# vor_add_on.net
KiCad netlist of a schematic drawn in EAGLE
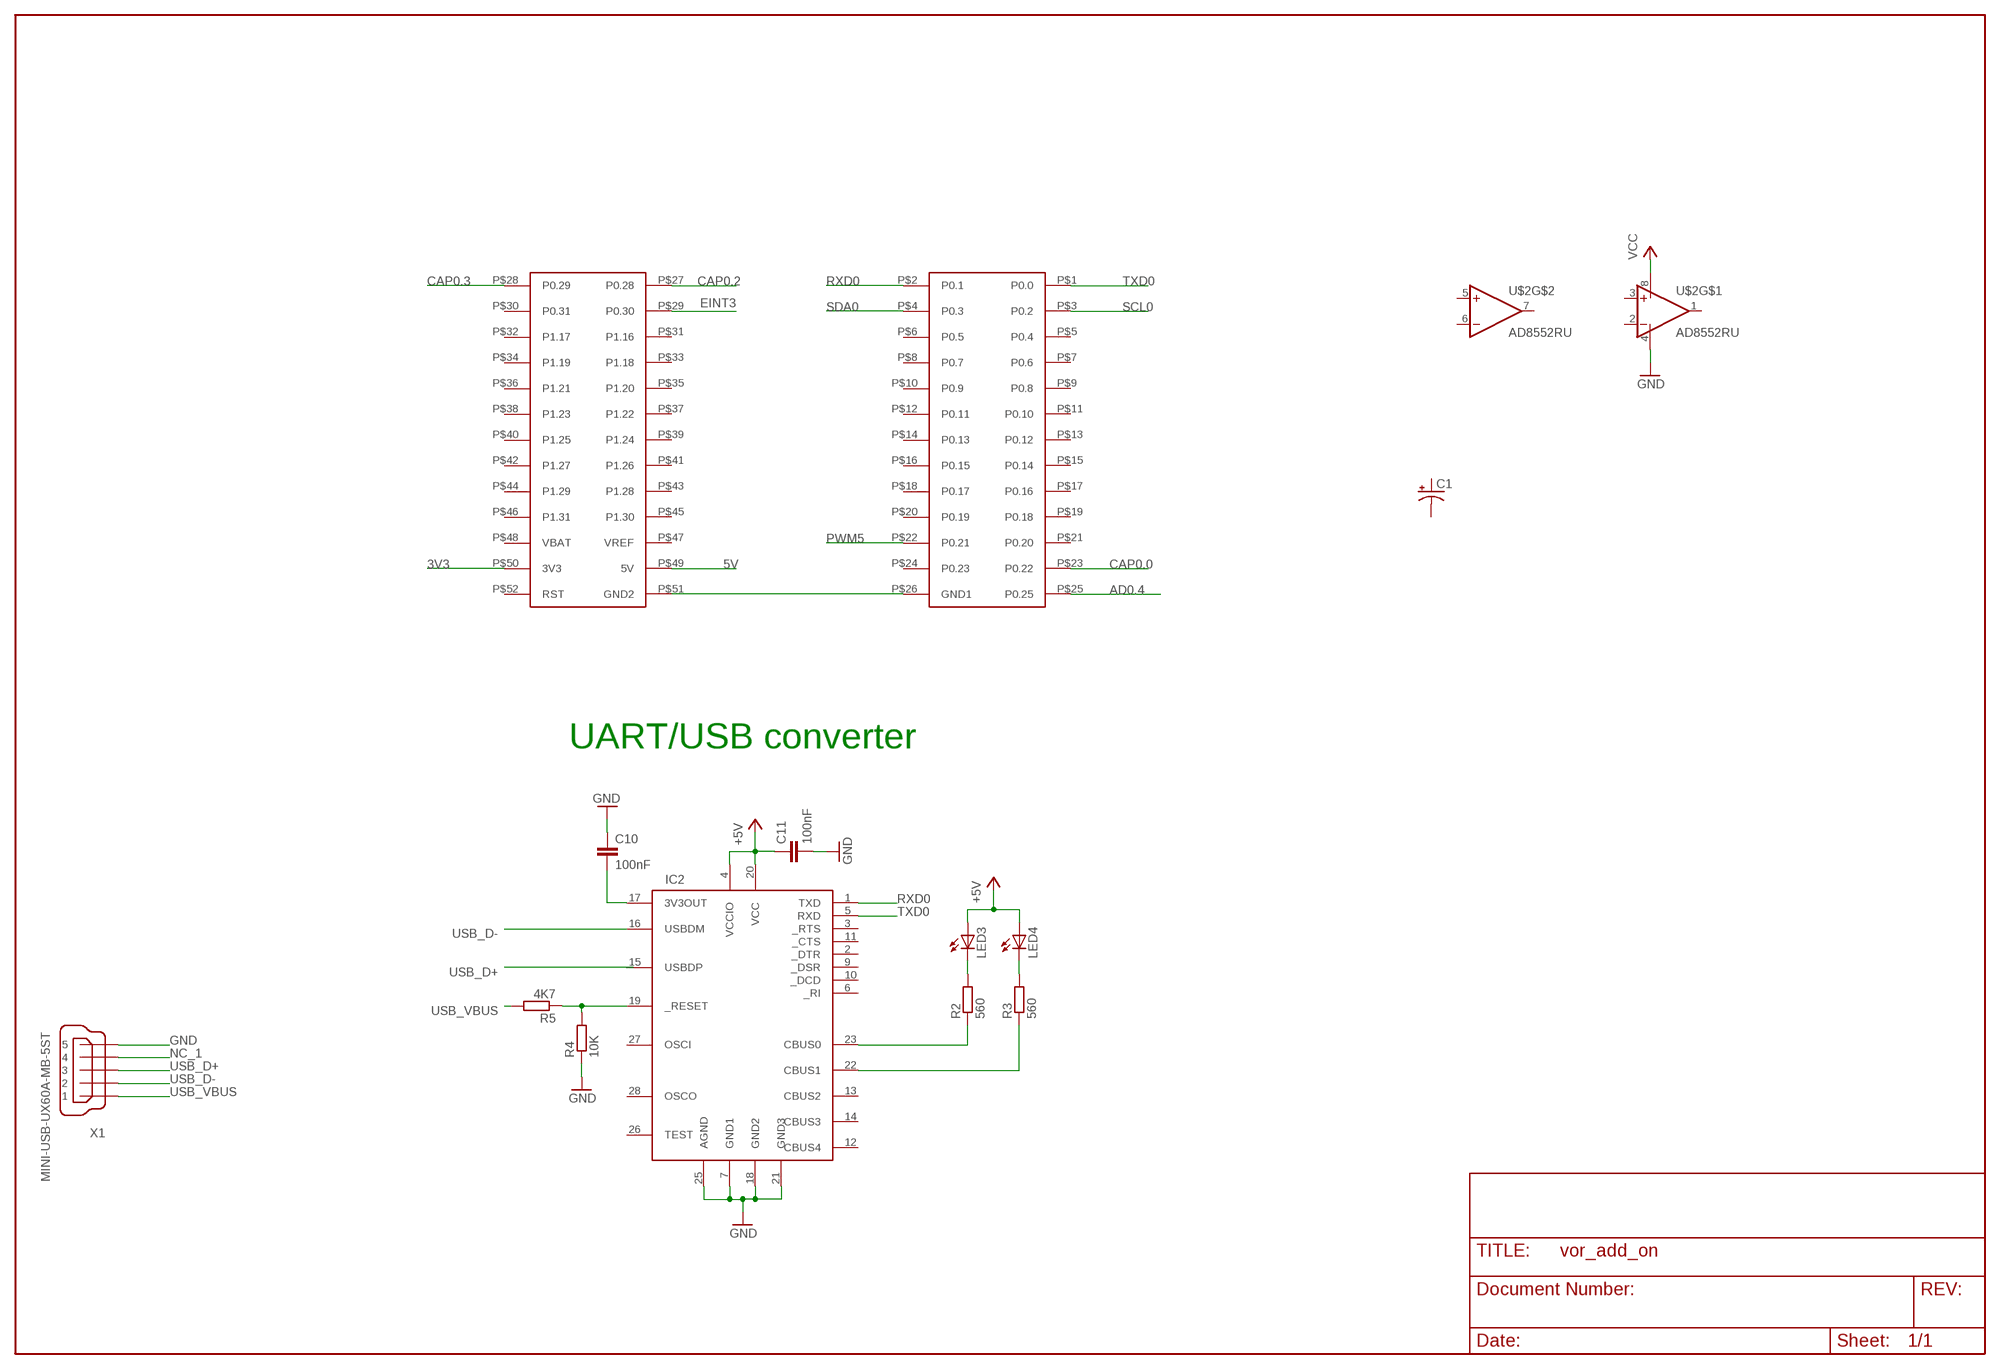
[diagram p0: schematic, sheet 1]

(export (version "E")
  (design (tool "Eeschema 10.0.6"))
  (components
    (comp (ref "C1")
      (value "CPOL-USCT7343")
      (footprint "eagle-import:CT7343")
      (libsource (lib "eagle-import") (part "CPOL-USCT7343"))
    )
    (comp (ref "C10")
      (value "100nF")
      (footprint "eagle-import:C0603K")
      (libsource (lib "eagle-import") (part "C-EUC0603K"))
    )
    (comp (ref "C11")
      (value "100nF")
      (footprint "eagle-import:C0603K")
      (libsource (lib "eagle-import") (part "C-EUC0603K"))
    )
    (comp (ref "IC2")
      (value "FT232RL")
      (footprint "eagle-import:SSOP28DB")
      (libsource (lib "eagle-import") (part "FT232RL"))
    )
    (comp (ref "LED3")
      (value "LEDCHIPLED_0805")
      (footprint "eagle-import:CHIPLED_0805")
      (libsource (lib "eagle-import") (part "LEDCHIPLED_0805"))
    )
    (comp (ref "LED4")
      (value "LEDCHIPLED_0805")
      (footprint "eagle-import:CHIPLED_0805")
      (libsource (lib "eagle-import") (part "LEDCHIPLED_0805"))
    )
    (comp (ref "R2")
      (value "560")
      (footprint "eagle-import:R0805")
      (libsource (lib "eagle-import") (part "R-EU_R0805"))
    )
    (comp (ref "R3")
      (value "560")
      (footprint "eagle-import:R0805")
      (libsource (lib "eagle-import") (part "R-EU_R0805"))
    )
    (comp (ref "R4")
      (value "10K")
      (footprint "eagle-import:R0603")
      (libsource (lib "eagle-import") (part "R-EU_R0603"))
    )
    (comp (ref "R5")
      (value "4K7")
      (footprint "eagle-import:R0603")
      (libsource (lib "eagle-import") (part "R-EU_R0603"))
    )
    (comp (ref "U$1")
      (value "OLIMEX_2148")
      (footprint "eagle-import:OLIMEX_2148")
      (libsource (lib "eagle-import") (part "OLIMEX_2148"))
    )
    (comp (ref "U$2")
      (value "AD8552RU")
      (footprint "eagle-import:TSSOP8")
      (libsource (lib "eagle-import") (part "AD8552RU"))
    )
    (comp (ref "X1")
      (value "MINI-USB-UX60A-MB-5ST")
      (footprint "eagle-import:UX60A-MB-5ST")
      (libsource (lib "eagle-import") (part "MINI-USB-UX60A-MB-5ST"))
    )
  )
  (nets
    (net (code "1") (name "+5V") (class "Default")
      (node (ref "C11") (pin "1") (pinfunction "1_1") (pintype "passive"))
      (node (ref "IC2") (pin "20") (pinfunction "VCC_20") (pintype "power_in"))
      (node (ref "IC2") (pin "4") (pinfunction "VCCIO_4") (pintype "power_in"))
      (node (ref "LED3") (pin "A") (pinfunction "A_A") (pintype "passive"))
      (node (ref "LED4") (pin "A") (pinfunction "A_A") (pintype "passive"))
    )
    (net (code "2") (name "/3V3") (class "Default")
      (node (ref "U$1") (pin "P$50") (pinfunction "3V3_P$50") (pintype "bidirectional"))
    )
    (net (code "3") (name "/5V") (class "Default")
      (node (ref "U$1") (pin "P$49") (pinfunction "5V_P$49") (pintype "bidirectional"))
    )
    (net (code "4") (name "/AD0.4") (class "Default")
      (node (ref "U$1") (pin "P$25") (pinfunction "P0.25_P$25") (pintype "bidirectional"))
    )
    (net (code "5") (name "/CAP0.0") (class "Default")
      (node (ref "U$1") (pin "P$23") (pinfunction "P0.22_P$23") (pintype "bidirectional"))
    )
    (net (code "6") (name "/CAP0.2") (class "Default")
      (node (ref "U$1") (pin "P$27") (pinfunction "P0.28_P$27") (pintype "bidirectional"))
    )
    (net (code "7") (name "/CAP0.3") (class "Default")
      (node (ref "U$1") (pin "P$28") (pinfunction "P0.29_P$28") (pintype "bidirectional"))
    )
    (net (code "8") (name "/EINT3") (class "Default")
      (node (ref "U$1") (pin "P$29") (pinfunction "P0.30_P$29") (pintype "bidirectional"))
    )
    (net (code "9") (name "/NC_1") (class "Default")
      (node (ref "X1") (pin "4") (pinfunction "4_4") (pintype "input"))
    )
    (net (code "10") (name "/PWM5") (class "Default")
      (node (ref "U$1") (pin "P$22") (pinfunction "P0.21_P$22") (pintype "bidirectional"))
    )
    (net (code "11") (name "/RXD0") (class "Default")
      (node (ref "IC2") (pin "1") (pinfunction "TXD_1") (pintype "output"))
      (node (ref "U$1") (pin "P$2") (pinfunction "P0.1_P$2") (pintype "bidirectional"))
    )
    (net (code "12") (name "/SCL0") (class "Default")
      (node (ref "U$1") (pin "P$3") (pinfunction "P0.2_P$3") (pintype "bidirectional"))
    )
    (net (code "13") (name "/SDA0") (class "Default")
      (node (ref "U$1") (pin "P$4") (pinfunction "P0.3_P$4") (pintype "bidirectional"))
    )
    (net (code "14") (name "/TXD0") (class "Default")
      (node (ref "IC2") (pin "5") (pinfunction "RXD_5") (pintype "input"))
      (node (ref "U$1") (pin "P$1") (pinfunction "P0.0_P$1") (pintype "bidirectional"))
    )
    (net (code "15") (name "/USB_D+") (class "Default")
      (node (ref "X1") (pin "3") (pinfunction "3_3") (pintype "input"))
    )
    (net (code "16") (name "/USB_D-") (class "Default")
      (node (ref "IC2") (pin "16") (pinfunction "USBDM_16") (pintype "bidirectional"))
      (node (ref "X1") (pin "2") (pinfunction "2_2") (pintype "input"))
    )
    (net (code "17") (name "/USB_VBUS") (class "Default")
      (node (ref "R5") (pin "2") (pinfunction "2_2") (pintype "passive"))
      (node (ref "X1") (pin "1") (pinfunction "1_1") (pintype "input"))
    )
    (net (code "18") (name "GND") (class "Default")
      (node (ref "C10") (pin "1") (pinfunction "1_1") (pintype "passive"))
      (node (ref "C11") (pin "2") (pinfunction "2_2") (pintype "passive"))
      (node (ref "IC2") (pin "18") (pinfunction "GND2_18") (pintype "power_in"))
      (node (ref "IC2") (pin "21") (pinfunction "GND3_21") (pintype "power_in"))
      (node (ref "IC2") (pin "25") (pinfunction "AGND_25") (pintype "power_in"))
      (node (ref "IC2") (pin "7") (pinfunction "GND1_7") (pintype "power_in"))
      (node (ref "R4") (pin "1") (pinfunction "1_1") (pintype "passive"))
      (node (ref "U$1") (pin "P$26") (pinfunction "GND1_P$26") (pintype "bidirectional"))
      (node (ref "U$1") (pin "P$51") (pinfunction "GND2_P$51") (pintype "bidirectional"))
      (node (ref "U$2") (pin "4") (pinfunction "V-_4") (pintype "power_in"))
      (node (ref "X1") (pin "5") (pinfunction "5_5") (pintype "input"))
    )
    (net (code "19") (name "Net-(IC2-3V3OUT)") (class "Default")
      (node (ref "C10") (pin "2") (pinfunction "2_2") (pintype "passive"))
      (node (ref "IC2") (pin "17") (pinfunction "3V3OUT_17") (pintype "output"))
    )
    (net (code "20") (name "Net-(IC2-CBUS0)") (class "Default")
      (node (ref "IC2") (pin "23") (pinfunction "CBUS0_23") (pintype "bidirectional"))
      (node (ref "R2") (pin "1") (pinfunction "1_1") (pintype "passive"))
    )
    (net (code "21") (name "Net-(IC2-CBUS1)") (class "Default")
      (node (ref "IC2") (pin "22") (pinfunction "CBUS1_22") (pintype "bidirectional"))
      (node (ref "R3") (pin "1") (pinfunction "1_1") (pintype "passive"))
    )
    (net (code "22") (name "Net-(IC2-_RESET)") (class "Default")
      (node (ref "IC2") (pin "19") (pinfunction "_RESET_19") (pintype "input"))
      (node (ref "R4") (pin "2") (pinfunction "2_2") (pintype "passive"))
      (node (ref "R5") (pin "1") (pinfunction "1_1") (pintype "passive"))
    )
    (net (code "23") (name "Net-(LED3-PadC)") (class "Default")
      (node (ref "LED3") (pin "C") (pinfunction "C_C") (pintype "passive"))
      (node (ref "R2") (pin "2") (pinfunction "2_2") (pintype "passive"))
    )
    (net (code "24") (name "Net-(LED4-PadC)") (class "Default")
      (node (ref "LED4") (pin "C") (pinfunction "C_C") (pintype "passive"))
      (node (ref "R3") (pin "2") (pinfunction "2_2") (pintype "passive"))
    )
    (net (code "25") (name "VCC") (class "Default")
      (node (ref "U$2") (pin "8") (pinfunction "V+_8") (pintype "power_in"))
    )
    (net (code "26") (name "unconnected-(C1-Pad+)") (class "Default")
      (node (ref "C1") (pin "+") (pinfunction "+_+") (pintype "passive"))
    )
    (net (code "27") (name "unconnected-(C1-Pad-)") (class "Default")
      (node (ref "C1") (pin "-") (pinfunction "-_-") (pintype "passive"))
    )
    (net (code "28") (name "unconnected-(IC2-CBUS2-Pad13)") (class "Default")
      (node (ref "IC2") (pin "13") (pinfunction "CBUS2_13") (pintype "bidirectional"))
    )
    (net (code "29") (name "unconnected-(IC2-CBUS3-Pad14)") (class "Default")
      (node (ref "IC2") (pin "14") (pinfunction "CBUS3_14") (pintype "bidirectional"))
    )
    (net (code "30") (name "unconnected-(IC2-CBUS4-Pad12)") (class "Default")
      (node (ref "IC2") (pin "12") (pinfunction "CBUS4_12") (pintype "bidirectional"))
    )
    (net (code "31") (name "unconnected-(IC2-OSCI-Pad27)") (class "Default")
      (node (ref "IC2") (pin "27") (pinfunction "OSCI_27") (pintype "input"))
    )
    (net (code "32") (name "unconnected-(IC2-OSCO-Pad28)") (class "Default")
      (node (ref "IC2") (pin "28") (pinfunction "OSCO_28") (pintype "output"))
    )
    (net (code "33") (name "unconnected-(IC2-TEST-Pad26)") (class "Default")
      (node (ref "IC2") (pin "26") (pinfunction "TEST_26") (pintype "input"))
    )
    (net (code "34") (name "unconnected-(IC2-USBDP-Pad15)") (class "Default")
      (node (ref "IC2") (pin "15") (pinfunction "USBDP_15") (pintype "bidirectional"))
    )
    (net (code "35") (name "unconnected-(IC2-_CTS-Pad11)") (class "Default")
      (node (ref "IC2") (pin "11") (pinfunction "_CTS_11") (pintype "input"))
    )
    (net (code "36") (name "unconnected-(IC2-_DCD-Pad10)") (class "Default")
      (node (ref "IC2") (pin "10") (pinfunction "_DCD_10") (pintype "input"))
    )
    (net (code "37") (name "unconnected-(IC2-_DSR-Pad9)") (class "Default")
      (node (ref "IC2") (pin "9") (pinfunction "_DSR_9") (pintype "input"))
    )
    (net (code "38") (name "unconnected-(IC2-_DTR-Pad2)") (class "Default")
      (node (ref "IC2") (pin "2") (pinfunction "_DTR_2") (pintype "output"))
    )
    (net (code "39") (name "unconnected-(IC2-_RI-Pad6)") (class "Default")
      (node (ref "IC2") (pin "6") (pinfunction "_RI_6") (pintype "input"))
    )
    (net (code "40") (name "unconnected-(IC2-_RTS-Pad3)") (class "Default")
      (node (ref "IC2") (pin "3") (pinfunction "_RTS_3") (pintype "output"))
    )
    (net (code "41") (name "unconnected-(U$1-P0.4-PadP$5)") (class "Default")
      (node (ref "U$1") (pin "P$5") (pinfunction "P0.4_P$5") (pintype "bidirectional"))
    )
    (net (code "42") (name "unconnected-(U$1-P0.5-PadP$6)") (class "Default")
      (node (ref "U$1") (pin "P$6") (pinfunction "P0.5_P$6") (pintype "bidirectional"))
    )
    (net (code "43") (name "unconnected-(U$1-P0.6-PadP$7)") (class "Default")
      (node (ref "U$1") (pin "P$7") (pinfunction "P0.6_P$7") (pintype "bidirectional"))
    )
    (net (code "44") (name "unconnected-(U$1-P0.7-PadP$8)") (class "Default")
      (node (ref "U$1") (pin "P$8") (pinfunction "P0.7_P$8") (pintype "bidirectional"))
    )
    (net (code "45") (name "unconnected-(U$1-P0.8-PadP$9)") (class "Default")
      (node (ref "U$1") (pin "P$9") (pinfunction "P0.8_P$9") (pintype "bidirectional"))
    )
    (net (code "46") (name "unconnected-(U$1-P0.9-PadP$10)") (class "Default")
      (node (ref "U$1") (pin "P$10") (pinfunction "P0.9_P$10") (pintype "bidirectional"))
    )
    (net (code "47") (name "unconnected-(U$1-P0.10-PadP$11)") (class "Default")
      (node (ref "U$1") (pin "P$11") (pinfunction "P0.10_P$11") (pintype "bidirectional"))
    )
    (net (code "48") (name "unconnected-(U$1-P0.11-PadP$12)") (class "Default")
      (node (ref "U$1") (pin "P$12") (pinfunction "P0.11_P$12") (pintype "bidirectional"))
    )
    (net (code "49") (name "unconnected-(U$1-P0.12-PadP$13)") (class "Default")
      (node (ref "U$1") (pin "P$13") (pinfunction "P0.12_P$13") (pintype "bidirectional"))
    )
    (net (code "50") (name "unconnected-(U$1-P0.13-PadP$14)") (class "Default")
      (node (ref "U$1") (pin "P$14") (pinfunction "P0.13_P$14") (pintype "bidirectional"))
    )
    (net (code "51") (name "unconnected-(U$1-P0.14-PadP$15)") (class "Default")
      (node (ref "U$1") (pin "P$15") (pinfunction "P0.14_P$15") (pintype "bidirectional"))
    )
    (net (code "52") (name "unconnected-(U$1-P0.15-PadP$16)") (class "Default")
      (node (ref "U$1") (pin "P$16") (pinfunction "P0.15_P$16") (pintype "bidirectional"))
    )
    (net (code "53") (name "unconnected-(U$1-P0.16-PadP$17)") (class "Default")
      (node (ref "U$1") (pin "P$17") (pinfunction "P0.16_P$17") (pintype "bidirectional"))
    )
    (net (code "54") (name "unconnected-(U$1-P0.17-PadP$18)") (class "Default")
      (node (ref "U$1") (pin "P$18") (pinfunction "P0.17_P$18") (pintype "bidirectional"))
    )
    (net (code "55") (name "unconnected-(U$1-P0.18-PadP$19)") (class "Default")
      (node (ref "U$1") (pin "P$19") (pinfunction "P0.18_P$19") (pintype "bidirectional"))
    )
    (net (code "56") (name "unconnected-(U$1-P0.19-PadP$20)") (class "Default")
      (node (ref "U$1") (pin "P$20") (pinfunction "P0.19_P$20") (pintype "bidirectional"))
    )
    (net (code "57") (name "unconnected-(U$1-P0.20-PadP$21)") (class "Default")
      (node (ref "U$1") (pin "P$21") (pinfunction "P0.20_P$21") (pintype "bidirectional"))
    )
    (net (code "58") (name "unconnected-(U$1-P0.23-PadP$24)") (class "Default")
      (node (ref "U$1") (pin "P$24") (pinfunction "P0.23_P$24") (pintype "bidirectional"))
    )
    (net (code "59") (name "unconnected-(U$1-P0.31-PadP$30)") (class "Default")
      (node (ref "U$1") (pin "P$30") (pinfunction "P0.31_P$30") (pintype "bidirectional"))
    )
    (net (code "60") (name "unconnected-(U$1-P1.16-PadP$31)") (class "Default")
      (node (ref "U$1") (pin "P$31") (pinfunction "P1.16_P$31") (pintype "bidirectional"))
    )
    (net (code "61") (name "unconnected-(U$1-P1.17-PadP$32)") (class "Default")
      (node (ref "U$1") (pin "P$32") (pinfunction "P1.17_P$32") (pintype "bidirectional"))
    )
    (net (code "62") (name "unconnected-(U$1-P1.18-PadP$33)") (class "Default")
      (node (ref "U$1") (pin "P$33") (pinfunction "P1.18_P$33") (pintype "bidirectional"))
    )
    (net (code "63") (name "unconnected-(U$1-P1.19-PadP$34)") (class "Default")
      (node (ref "U$1") (pin "P$34") (pinfunction "P1.19_P$34") (pintype "bidirectional"))
    )
    (net (code "64") (name "unconnected-(U$1-P1.20-PadP$35)") (class "Default")
      (node (ref "U$1") (pin "P$35") (pinfunction "P1.20_P$35") (pintype "bidirectional"))
    )
    (net (code "65") (name "unconnected-(U$1-P1.21-PadP$36)") (class "Default")
      (node (ref "U$1") (pin "P$36") (pinfunction "P1.21_P$36") (pintype "bidirectional"))
    )
    (net (code "66") (name "unconnected-(U$1-P1.22-PadP$37)") (class "Default")
      (node (ref "U$1") (pin "P$37") (pinfunction "P1.22_P$37") (pintype "bidirectional"))
    )
    (net (code "67") (name "unconnected-(U$1-P1.23-PadP$38)") (class "Default")
      (node (ref "U$1") (pin "P$38") (pinfunction "P1.23_P$38") (pintype "bidirectional"))
    )
    (net (code "68") (name "unconnected-(U$1-P1.24-PadP$39)") (class "Default")
      (node (ref "U$1") (pin "P$39") (pinfunction "P1.24_P$39") (pintype "bidirectional"))
    )
    (net (code "69") (name "unconnected-(U$1-P1.25-PadP$40)") (class "Default")
      (node (ref "U$1") (pin "P$40") (pinfunction "P1.25_P$40") (pintype "bidirectional"))
    )
    (net (code "70") (name "unconnected-(U$1-P1.26-PadP$41)") (class "Default")
      (node (ref "U$1") (pin "P$41") (pinfunction "P1.26_P$41") (pintype "bidirectional"))
    )
    (net (code "71") (name "unconnected-(U$1-P1.27-PadP$42)") (class "Default")
      (node (ref "U$1") (pin "P$42") (pinfunction "P1.27_P$42") (pintype "bidirectional"))
    )
    (net (code "72") (name "unconnected-(U$1-P1.28-PadP$43)") (class "Default")
      (node (ref "U$1") (pin "P$43") (pinfunction "P1.28_P$43") (pintype "bidirectional"))
    )
    (net (code "73") (name "unconnected-(U$1-P1.29-PadP$44)") (class "Default")
      (node (ref "U$1") (pin "P$44") (pinfunction "P1.29_P$44") (pintype "bidirectional"))
    )
    (net (code "74") (name "unconnected-(U$1-P1.30-PadP$45)") (class "Default")
      (node (ref "U$1") (pin "P$45") (pinfunction "P1.30_P$45") (pintype "bidirectional"))
    )
    (net (code "75") (name "unconnected-(U$1-P1.31-PadP$46)") (class "Default")
      (node (ref "U$1") (pin "P$46") (pinfunction "P1.31_P$46") (pintype "bidirectional"))
    )
    (net (code "76") (name "unconnected-(U$1-RST-PadP$52)") (class "Default")
      (node (ref "U$1") (pin "P$52") (pinfunction "RST_P$52") (pintype "bidirectional"))
    )
    (net (code "77") (name "unconnected-(U$1-VBAT-PadP$48)") (class "Default")
      (node (ref "U$1") (pin "P$48") (pinfunction "VBAT_P$48") (pintype "bidirectional"))
    )
    (net (code "78") (name "unconnected-(U$1-VREF-PadP$47)") (class "Default")
      (node (ref "U$1") (pin "P$47") (pinfunction "VREF_P$47") (pintype "bidirectional"))
    )
    (net (code "79") (name "unconnected-(U$2A-+IN-Pad3)") (class "Default")
      (node (ref "U$2") (pin "3") (pinfunction "+IN_3") (pintype "input"))
    )
    (net (code "80") (name "unconnected-(U$2A--IN-Pad2)") (class "Default")
      (node (ref "U$2") (pin "2") (pinfunction "-IN_2") (pintype "input"))
    )
    (net (code "81") (name "unconnected-(U$2A-OUT-Pad1)") (class "Default")
      (node (ref "U$2") (pin "1") (pinfunction "OUT_1") (pintype "output"))
    )
    (net (code "82") (name "unconnected-(U$2B-+IN-Pad5)") (class "Default")
      (node (ref "U$2") (pin "5") (pinfunction "+IN_5") (pintype "input"))
    )
    (net (code "83") (name "unconnected-(U$2B--IN-Pad6)") (class "Default")
      (node (ref "U$2") (pin "6") (pinfunction "-IN_6") (pintype "input"))
    )
    (net (code "84") (name "unconnected-(U$2B-OUT-Pad7)") (class "Default")
      (node (ref "U$2") (pin "7") (pinfunction "OUT_7") (pintype "output"))
    )
  )
)
